# 12mPCIe.net
KiCad netlist of a schematic drawn in Altium Designer
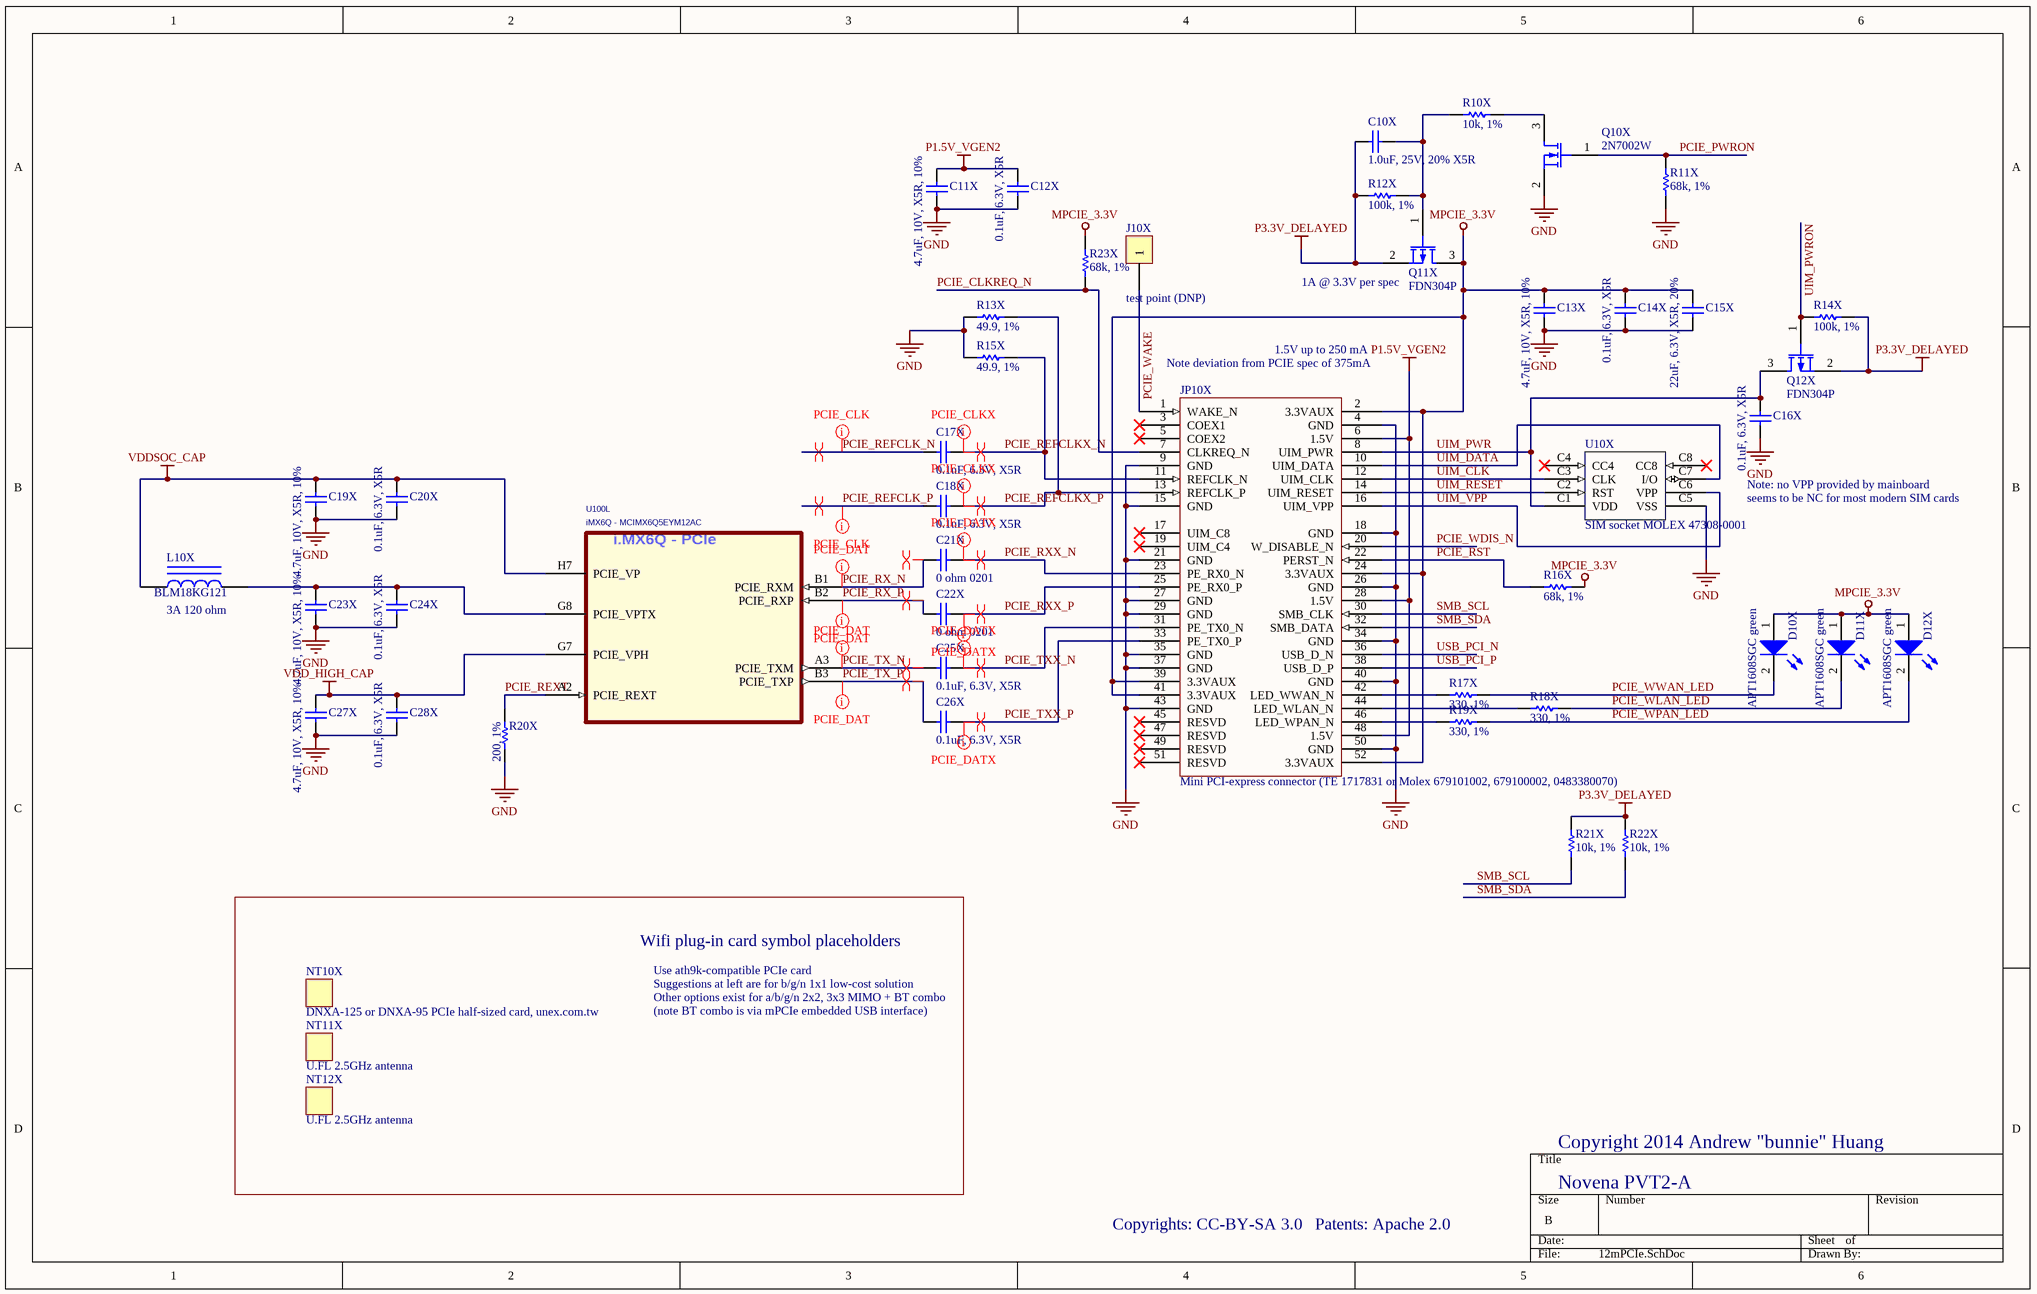
[diagram p0: 12mPCIe.SchDoc]

(export (version "E")
  (design (tool "Eeschema 10.0.6"))
  (components
    (comp (ref "C10X")
      (value "1.0uF, 25V, 20% X5R")
      (footprint "CAPC1608N")
      (description "Capacitor (Semiconductor SIM Model)")
      (fields (field (name "PUBLISHER") "Altium Limited"))
      (libsource (lib "Miscellaneous Devices") (part "Cap Semi"))
    )
    (comp (ref "C11X")
      (value "4.7uF, 10V, X5R, 10%")
      (footprint "CAPC1608N")
      (description "Capacitor (Semiconductor SIM Model)")
      (fields (field (name "PUBLISHER") "Altium Limited"))
      (libsource (lib "Miscellaneous Devices") (part "Cap Semi"))
    )
    (comp (ref "C12X")
      (value "0.1uF, 6.3V, X5R")
      (footprint "CAPC0603N_B")
      (description "Capacitor (Semiconductor SIM Model)")
      (fields (field (name "PUBLISHER") "Altium Limited"))
      (libsource (lib "Miscellaneous Devices") (part "Cap Semi"))
    )
    (comp (ref "C13X")
      (value "4.7uF, 10V, X5R, 10%")
      (footprint "CAPC1608N")
      (description "Capacitor (Semiconductor SIM Model)")
      (fields (field (name "PUBLISHER") "Altium Limited"))
      (libsource (lib "Miscellaneous Devices") (part "Cap Semi"))
    )
    (comp (ref "C14X")
      (value "0.1uF, 6.3V, X5R")
      (footprint "CAPC0603N_B")
      (description "Capacitor (Semiconductor SIM Model)")
      (fields (field (name "PUBLISHER") "Altium Limited"))
      (libsource (lib "Miscellaneous Devices") (part "Cap Semi"))
    )
    (comp (ref "C15X")
      (value "22uF, 6.3V, X5R, 20%")
      (footprint "CAPC1608N_HD")
      (description "Capacitor (Semiconductor SIM Model)")
      (fields (field (name "PUBLISHER") "Altium Limited"))
      (libsource (lib "Miscellaneous Devices") (part "Cap Semi"))
    )
    (comp (ref "C16X")
      (value "0.1uF, 6.3V, X5R")
      (footprint "CAPC0603N_B")
      (description "Capacitor (Semiconductor SIM Model)")
      (fields (field (name "PUBLISHER") "Altium Limited"))
      (libsource (lib "Miscellaneous Devices") (part "Cap Semi"))
    )
    (comp (ref "C17X")
      (value "0.1uF, 6.3V, X5R")
      (footprint "CAPC0603N_B")
      (description "Capacitor (Semiconductor SIM Model)")
      (fields (field (name "PUBLISHER") "Altium Limited"))
      (libsource (lib "Miscellaneous Devices") (part "Cap Semi"))
    )
    (comp (ref "C18X")
      (value "0.1uF, 6.3V, X5R")
      (footprint "CAPC0603N_B")
      (description "Capacitor (Semiconductor SIM Model)")
      (fields (field (name "PUBLISHER") "Altium Limited"))
      (libsource (lib "Miscellaneous Devices") (part "Cap Semi"))
    )
    (comp (ref "C19X")
      (value "4.7uF, 10V, X5R, 10%")
      (footprint "CAPC1608N_HD")
      (description "Capacitor (Semiconductor SIM Model)")
      (fields (field (name "PUBLISHER") "Altium Limited"))
      (libsource (lib "Miscellaneous Devices") (part "Cap Semi"))
    )
    (comp (ref "C20X")
      (value "0.1uF, 6.3V, X5R")
      (footprint "CAPC0603N_B")
      (description "Capacitor (Semiconductor SIM Model)")
      (fields (field (name "PUBLISHER") "Altium Limited"))
      (libsource (lib "Miscellaneous Devices") (part "Cap Semi"))
    )
    (comp (ref "C21X")
      (value "0 ohm 0201")
      (footprint "CAPC0603N_B")
      (description "Capacitor (Semiconductor SIM Model)")
      (fields (field (name "PUBLISHER") "Altium Limited"))
      (libsource (lib "Miscellaneous Devices") (part "Cap Semi"))
    )
    (comp (ref "C22X")
      (value "0 ohm 0201")
      (footprint "CAPC0603N_B")
      (description "Capacitor (Semiconductor SIM Model)")
      (fields (field (name "PUBLISHER") "Altium Limited"))
      (libsource (lib "Miscellaneous Devices") (part "Cap Semi"))
    )
    (comp (ref "C23X")
      (value "4.7uF, 10V, X5R, 10%")
      (footprint "CAPC1608N_HD")
      (description "Capacitor (Semiconductor SIM Model)")
      (fields (field (name "PUBLISHER") "Altium Limited"))
      (libsource (lib "Miscellaneous Devices") (part "Cap Semi"))
    )
    (comp (ref "C24X")
      (value "0.1uF, 6.3V, X5R")
      (footprint "CAPC0603N_B")
      (description "Capacitor (Semiconductor SIM Model)")
      (fields (field (name "PUBLISHER") "Altium Limited"))
      (libsource (lib "Miscellaneous Devices") (part "Cap Semi"))
    )
    (comp (ref "C25X")
      (value "0.1uF, 6.3V, X5R")
      (footprint "CAPC0603N_B")
      (description "Capacitor (Semiconductor SIM Model)")
      (fields (field (name "PUBLISHER") "Altium Limited"))
      (libsource (lib "Miscellaneous Devices") (part "Cap Semi"))
    )
    (comp (ref "C26X")
      (value "0.1uF, 6.3V, X5R")
      (footprint "CAPC0603N_B")
      (description "Capacitor (Semiconductor SIM Model)")
      (fields (field (name "PUBLISHER") "Altium Limited"))
      (libsource (lib "Miscellaneous Devices") (part "Cap Semi"))
    )
    (comp (ref "C27X")
      (value "4.7uF, 10V, X5R, 10%")
      (footprint "CAPC1608N_HD")
      (description "Capacitor (Semiconductor SIM Model)")
      (fields (field (name "PUBLISHER") "Altium Limited"))
      (libsource (lib "Miscellaneous Devices") (part "Cap Semi"))
    )
    (comp (ref "C28X")
      (value "0.1uF, 6.3V, X5R")
      (footprint "CAPC0603N_B")
      (description "Capacitor (Semiconductor SIM Model)")
      (fields (field (name "PUBLISHER") "Altium Limited"))
      (libsource (lib "Miscellaneous Devices") (part "Cap Semi"))
    )
    (comp (ref "D10X")
      (value "APT1608SGC green")
      (footprint "CD1608-0603")
      (description "Typical RED, GREEN, YELLOW, AMBER GaAs LED")
      (fields (field (name "PUBLISHER") "Altium Limited"))
      (libsource (lib "Miscellaneous Devices") (part "LED2"))
    )
    (comp (ref "D11X")
      (value "APT1608SGC green")
      (footprint "CD1608-0603")
      (description "Typical RED, GREEN, YELLOW, AMBER GaAs LED")
      (fields (field (name "PUBLISHER") "Altium Limited"))
      (libsource (lib "Miscellaneous Devices") (part "LED2"))
    )
    (comp (ref "D12X")
      (value "APT1608SGC green")
      (footprint "CD1608-0603")
      (description "Typical RED, GREEN, YELLOW, AMBER GaAs LED")
      (fields (field (name "PUBLISHER") "Altium Limited"))
      (libsource (lib "Miscellaneous Devices") (part "LED2"))
    )
    (comp (ref "J10X")
      (value "test point (DNP)")
      (footprint "TP_SMT_38mil")
      (description "Connector")
      (libsource (lib "*") (part "CON1"))
    )
    (comp (ref "JP10X")
      (value "Mini PCI-express connector (TE 1717831 or Molex 679101002, 679100002, 0483380070)")
      (footprint "MPCI_FULL_TE_1717831")
      (description "Mini PCI-express, e.g. TE 1717831")
      (libsource (lib "commonsch") (part "MINI_PCIE"))
    )
    (comp (ref "L10X")
      (value "BLM18KG121")
      (footprint "INDC1608AN")
      (description "Magnetic-Core Inductor")
      (fields (field (name "ALTIUM_VALUE") "3A 120 ohm") (field (name "PUBLISHER") "Altium Limited"))
      (libsource (lib "Miscellaneous Devices") (part "Inductor Iron"))
    )
    (comp (ref "NT10X")
      (value "DNXA-125 or DNXA-95 PCIe half-sized card, unex.com.tw")
      (description "Placeholder for non-electrical BOM items")
      (libsource (lib "commonsch") (part "NOTE"))
    )
    (comp (ref "NT11X")
      (value "U.FL 2.5GHz antenna")
      (description "Placeholder for non-electrical BOM items")
      (libsource (lib "commonsch") (part "NOTE"))
    )
    (comp (ref "NT12X")
      (value "U.FL 2.5GHz antenna")
      (description "Placeholder for non-electrical BOM items")
      (libsource (lib "commonsch") (part "NOTE"))
    )
    (comp (ref "Q10X")
      (value "2N7002W")
      (footprint "SOT323-3AN")
      (description "N-Channel MOSFET")
      (fields (field (name "PUBLISHER") "Altium Limited"))
      (libsource (lib "Miscellaneous Devices") (part "MOSFET-N"))
    )
    (comp (ref "Q11X")
      (value "FDN304P")
      (footprint "SOT23-3N")
      (description "P-Channel MOSFET")
      (fields (field (name "PUBLISHER") "Altium Limited"))
      (libsource (lib "Miscellaneous Devices") (part "MOSFET-P"))
    )
    (comp (ref "Q12X")
      (value "FDN304P")
      (footprint "SOT23-3N")
      (description "P-Channel MOSFET")
      (fields (field (name "PUBLISHER") "Altium Limited"))
      (libsource (lib "Miscellaneous Devices") (part "MOSFET-P"))
    )
    (comp (ref "R10X")
      (value "10k, 1%")
      (footprint "RESC1005N")
      (description "Resistor")
      (fields (field (name "PUBLISHER") "Altium Limited"))
      (libsource (lib "Miscellaneous Devices") (part "Res1"))
    )
    (comp (ref "R11X")
      (value "68k, 1%")
      (footprint "RESC1005N")
      (description "Resistor")
      (fields (field (name "PUBLISHER") "Altium Limited"))
      (libsource (lib "Miscellaneous Devices") (part "Res1"))
    )
    (comp (ref "R12X")
      (value "100k, 1%")
      (footprint "RESC1005N")
      (description "Resistor")
      (fields (field (name "PUBLISHER") "Altium Limited"))
      (libsource (lib "Miscellaneous Devices") (part "Res1"))
    )
    (comp (ref "R13X")
      (value "49.9, 1%")
      (footprint "RESC1005N")
      (description "Resistor")
      (fields (field (name "PUBLISHER") "Altium Limited"))
      (libsource (lib "Miscellaneous Devices") (part "Res1"))
    )
    (comp (ref "R14X")
      (value "100k, 1%")
      (footprint "RESC1005N")
      (description "Resistor")
      (fields (field (name "PUBLISHER") "Altium Limited"))
      (libsource (lib "Miscellaneous Devices") (part "Res1"))
    )
    (comp (ref "R15X")
      (value "49.9, 1%")
      (footprint "RESC1005N")
      (description "Resistor")
      (fields (field (name "PUBLISHER") "Altium Limited"))
      (libsource (lib "Miscellaneous Devices") (part "Res1"))
    )
    (comp (ref "R16X")
      (value "68k, 1%")
      (footprint "RESC1005N")
      (description "Resistor")
      (fields (field (name "PUBLISHER") "Altium Limited"))
      (libsource (lib "Miscellaneous Devices") (part "Res1"))
    )
    (comp (ref "R17X")
      (value "330, 1%")
      (footprint "RESC1005N")
      (description "Resistor")
      (fields (field (name "PUBLISHER") "Altium Limited"))
      (libsource (lib "Miscellaneous Devices") (part "Res1"))
    )
    (comp (ref "R18X")
      (value "330, 1%")
      (footprint "RESC1005N")
      (description "Resistor")
      (fields (field (name "PUBLISHER") "Altium Limited"))
      (libsource (lib "Miscellaneous Devices") (part "Res1"))
    )
    (comp (ref "R19X")
      (value "330, 1%")
      (footprint "RESC1005N")
      (description "Resistor")
      (fields (field (name "PUBLISHER") "Altium Limited"))
      (libsource (lib "Miscellaneous Devices") (part "Res1"))
    )
    (comp (ref "R20X")
      (value "200, 1%")
      (footprint "RESC1005N")
      (description "Resistor")
      (fields (field (name "PUBLISHER") "Altium Limited"))
      (libsource (lib "Miscellaneous Devices") (part "Res1"))
    )
    (comp (ref "R21X")
      (value "10k, 1%")
      (footprint "RESC1005N")
      (description "Resistor")
      (fields (field (name "PUBLISHER") "Altium Limited"))
      (libsource (lib "Miscellaneous Devices") (part "Res1"))
    )
    (comp (ref "R22X")
      (value "10k, 1%")
      (footprint "RESC1005N")
      (description "Resistor")
      (fields (field (name "PUBLISHER") "Altium Limited"))
      (libsource (lib "Miscellaneous Devices") (part "Res1"))
    )
    (comp (ref "R23X")
      (value "68k, 1%")
      (footprint "RESC1005N")
      (description "Resistor")
      (fields (field (name "PUBLISHER") "Altium Limited"))
      (libsource (lib "Miscellaneous Devices") (part "Res1"))
    )
    (comp (ref "U10X")
      (value "SIM socket MOLEX 47308-0001")
      (footprint "MOLEX_SIM_47308-001")
      (description "ISO 7816 SIM card socket")
      (libsource (lib "commonsch") (part "ISO7816 (SIM card)"))
    )
    (comp (ref "U100")
      (value "iMX6Q - MCIMX6Q5EYM12AC")
      (description "PCIMX6Q5EVT10AC")
      (libsource (lib "*") (part "PCIMX6Q6VV1A"))
    )
  )
  (nets
    (net (code "1") (name "/PCIE_CLKREQ_N") (class "Default")
      (node (ref "JP10X") (pin "7") (pinfunction "CLKREQ_N_7") (pintype "passive"))
      (node (ref "R23X") (pin "1") (pinfunction "1_1") (pintype "passive"))
    )
    (net (code "2") (name "/PCIE_PWRON") (class "Default")
      (node (ref "Q10X") (pin "1") (pinfunction "G_1") (pintype "passive"))
      (node (ref "R11X") (pin "1") (pinfunction "1_1") (pintype "passive"))
    )
    (net (code "3") (name "/PCIE_REFCLKX_N") (class "Default")
      (node (ref "C17X") (pin "1") (pinfunction "1_1") (pintype "passive"))
      (node (ref "JP10X") (pin "11") (pinfunction "REFCLK_N_11") (pintype "input"))
      (node (ref "R15X") (pin "1") (pinfunction "1_1") (pintype "passive"))
    )
    (net (code "4") (name "/PCIE_REFCLKX_P") (class "Default")
      (node (ref "C18X") (pin "1") (pinfunction "1_1") (pintype "passive"))
      (node (ref "JP10X") (pin "13") (pinfunction "REFCLK_P_13") (pintype "input"))
      (node (ref "R13X") (pin "1") (pinfunction "1_1") (pintype "passive"))
    )
    (net (code "5") (name "/PCIE_REFCLK_N") (class "Default")
      (node (ref "C17X") (pin "2") (pinfunction "2_2") (pintype "passive"))
    )
    (net (code "6") (name "/PCIE_REFCLK_P") (class "Default")
      (node (ref "C18X") (pin "2") (pinfunction "2_2") (pintype "passive"))
    )
    (net (code "7") (name "/PCIE_REXT") (class "Default")
      (node (ref "R20X") (pin "2") (pinfunction "2_2") (pintype "passive"))
      (node (ref "U100") (pin "A2") (pinfunction "PCIE_REXT_A2") (pintype "input"))
    )
    (net (code "8") (name "/PCIE_RST") (class "Default")
      (node (ref "JP10X") (pin "22") (pinfunction "PERST_N_22") (pintype "input"))
      (node (ref "R16X") (pin "2") (pinfunction "2_2") (pintype "passive"))
    )
    (net (code "9") (name "/PCIE_RXX_N") (class "Default")
      (node (ref "C21X") (pin "1") (pinfunction "1_1") (pintype "passive"))
      (node (ref "JP10X") (pin "23") (pinfunction "PE_RX0_N_23") (pintype "passive"))
    )
    (net (code "10") (name "/PCIE_RXX_P") (class "Default")
      (node (ref "C22X") (pin "1") (pinfunction "1_1") (pintype "passive"))
      (node (ref "JP10X") (pin "25") (pinfunction "PE_RX0_P_25") (pintype "passive"))
    )
    (net (code "11") (name "/PCIE_RX_N") (class "Default")
      (node (ref "C21X") (pin "2") (pinfunction "2_2") (pintype "passive"))
      (node (ref "U100") (pin "B1") (pinfunction "PCIE_RXM_B1") (pintype "input"))
    )
    (net (code "12") (name "/PCIE_RX_P") (class "Default")
      (node (ref "C22X") (pin "2") (pinfunction "2_2") (pintype "passive"))
      (node (ref "U100") (pin "B2") (pinfunction "PCIE_RXP_B2") (pintype "input"))
    )
    (net (code "13") (name "/PCIE_TXX_N") (class "Default")
      (node (ref "C25X") (pin "1") (pinfunction "1_1") (pintype "passive"))
      (node (ref "JP10X") (pin "31") (pinfunction "PE_TX0_N_31") (pintype "passive"))
    )
    (net (code "14") (name "/PCIE_TXX_P") (class "Default")
      (node (ref "C26X") (pin "1") (pinfunction "1_1") (pintype "passive"))
      (node (ref "JP10X") (pin "33") (pinfunction "PE_TX0_P_33") (pintype "passive"))
    )
    (net (code "15") (name "/PCIE_TX_N") (class "Default")
      (node (ref "C25X") (pin "2") (pinfunction "2_2") (pintype "passive"))
      (node (ref "U100") (pin "A3") (pinfunction "PCIE_TXM_A3") (pintype "output"))
    )
    (net (code "16") (name "/PCIE_TX_P") (class "Default")
      (node (ref "C26X") (pin "2") (pinfunction "2_2") (pintype "passive"))
      (node (ref "U100") (pin "B3") (pinfunction "PCIE_TXP_B3") (pintype "output"))
    )
    (net (code "17") (name "/PCIE_WAKE") (class "Default")
      (node (ref "J10X") (pin "1") (pinfunction "1_1") (pintype "passive"))
      (node (ref "JP10X") (pin "1") (pinfunction "WAKE_N_1") (pintype "input"))
    )
    (net (code "18") (name "/PCIE_WDIS_N") (class "Default")
      (node (ref "JP10X") (pin "20") (pinfunction "W_DISABLE_N_20") (pintype "input"))
    )
    (net (code "19") (name "/PCIE_WLAN_LED") (class "Default")
      (node (ref "D11X") (pin "2") (pinfunction "K_2") (pintype "passive"))
      (node (ref "R18X") (pin "2") (pinfunction "2_2") (pintype "passive"))
    )
    (net (code "20") (name "/PCIE_WPAN_LED") (class "Default")
      (node (ref "D12X") (pin "2") (pinfunction "K_2") (pintype "passive"))
      (node (ref "R19X") (pin "2") (pinfunction "2_2") (pintype "passive"))
    )
    (net (code "21") (name "/PCIE_WWAN_LED") (class "Default")
      (node (ref "D10X") (pin "2") (pinfunction "K_2") (pintype "passive"))
      (node (ref "R17X") (pin "2") (pinfunction "2_2") (pintype "passive"))
    )
    (net (code "22") (name "/SMB_SCL") (class "Default")
      (node (ref "JP10X") (pin "30") (pinfunction "SMB_CLK_30") (pintype "input"))
      (node (ref "R21X") (pin "1") (pinfunction "1_1") (pintype "passive"))
    )
    (net (code "23") (name "/SMB_SDA") (class "Default")
      (node (ref "JP10X") (pin "32") (pinfunction "SMB_DATA_32") (pintype "input"))
      (node (ref "R22X") (pin "1") (pinfunction "1_1") (pintype "passive"))
    )
    (net (code "24") (name "/UIM_CLK") (class "Default")
      (node (ref "JP10X") (pin "12") (pinfunction "UIM_CLK_12") (pintype "passive"))
      (node (ref "U10X") (pin "C3") (pinfunction "CLK_C3") (pintype "input"))
    )
    (net (code "25") (name "/UIM_DATA") (class "Default")
      (node (ref "JP10X") (pin "10") (pinfunction "UIM_DATA_10") (pintype "passive"))
      (node (ref "U10X") (pin "C7") (pinfunction "I/O_C7") (pintype "bidirectional"))
    )
    (net (code "26") (name "/UIM_PWR") (class "Default")
      (node (ref "C16X") (pin "1") (pinfunction "1_1") (pintype "passive"))
      (node (ref "JP10X") (pin "8") (pinfunction "UIM_PWR_8") (pintype "passive"))
      (node (ref "Q12X") (pin "3") (pinfunction "D_3") (pintype "passive"))
      (node (ref "U10X") (pin "C1") (pinfunction "VDD_C1") (pintype "power_in"))
    )
    (net (code "27") (name "/UIM_PWRON") (class "Default")
      (node (ref "Q12X") (pin "1") (pinfunction "G_1") (pintype "passive"))
      (node (ref "R14X") (pin "2") (pinfunction "2_2") (pintype "passive"))
    )
    (net (code "28") (name "/UIM_RESET") (class "Default")
      (node (ref "JP10X") (pin "14") (pinfunction "UIM_RESET_14") (pintype "passive"))
      (node (ref "U10X") (pin "C2") (pinfunction "RST_C2") (pintype "input"))
    )
    (net (code "29") (name "/UIM_VPP") (class "Default")
      (node (ref "JP10X") (pin "16") (pinfunction "UIM_VPP_16") (pintype "passive"))
      (node (ref "U10X") (pin "C6") (pinfunction "VPP_C6") (pintype "power_in"))
    )
    (net (code "30") (name "/USB_PCI_N") (class "Default")
      (node (ref "JP10X") (pin "36") (pinfunction "USB_D_N_36") (pintype "passive"))
    )
    (net (code "31") (name "/USB_PCI_P") (class "Default")
      (node (ref "JP10X") (pin "38") (pinfunction "USB_D_P_38") (pintype "passive"))
    )
    (net (code "32") (name "GND") (class "Default")
      (node (ref "C11X") (pin "2") (pinfunction "2_2") (pintype "passive"))
      (node (ref "C12X") (pin "2") (pinfunction "2_2") (pintype "passive"))
      (node (ref "C13X") (pin "2") (pinfunction "2_2") (pintype "passive"))
      (node (ref "C14X") (pin "2") (pinfunction "2_2") (pintype "passive"))
      (node (ref "C15X") (pin "2") (pinfunction "2_2") (pintype "passive"))
      (node (ref "C16X") (pin "2") (pinfunction "2_2") (pintype "passive"))
      (node (ref "C19X") (pin "2") (pinfunction "2_2") (pintype "passive"))
      (node (ref "C20X") (pin "2") (pinfunction "2_2") (pintype "passive"))
      (node (ref "C23X") (pin "2") (pinfunction "2_2") (pintype "passive"))
      (node (ref "C24X") (pin "2") (pinfunction "2_2") (pintype "passive"))
      (node (ref "C27X") (pin "2") (pinfunction "2_2") (pintype "passive"))
      (node (ref "C28X") (pin "2") (pinfunction "2_2") (pintype "passive"))
      (node (ref "JP10X") (pin "15") (pinfunction "GND_15") (pintype "power_in"))
      (node (ref "JP10X") (pin "18") (pinfunction "GND_18") (pintype "power_in"))
      (node (ref "JP10X") (pin "21") (pinfunction "GND_21") (pintype "power_in"))
      (node (ref "JP10X") (pin "26") (pinfunction "GND_26") (pintype "power_in"))
      (node (ref "JP10X") (pin "27") (pinfunction "GND_27") (pintype "power_in"))
      (node (ref "JP10X") (pin "29") (pinfunction "GND_29") (pintype "power_in"))
      (node (ref "JP10X") (pin "34") (pinfunction "GND_34") (pintype "power_in"))
      (node (ref "JP10X") (pin "35") (pinfunction "GND_35") (pintype "power_in"))
      (node (ref "JP10X") (pin "37") (pinfunction "GND_37") (pintype "power_in"))
      (node (ref "JP10X") (pin "4") (pinfunction "GND_4") (pintype "power_in"))
      (node (ref "JP10X") (pin "40") (pinfunction "GND_40") (pintype "power_in"))
      (node (ref "JP10X") (pin "43") (pinfunction "GND_43") (pintype "power_in"))
      (node (ref "JP10X") (pin "50") (pinfunction "GND_50") (pintype "power_in"))
      (node (ref "JP10X") (pin "9") (pinfunction "GND_9") (pintype "power_in"))
      (node (ref "Q10X") (pin "2") (pinfunction "S_2") (pintype "passive"))
      (node (ref "R11X") (pin "2") (pinfunction "2_2") (pintype "passive"))
      (node (ref "R13X") (pin "2") (pinfunction "2_2") (pintype "passive"))
      (node (ref "R15X") (pin "2") (pinfunction "2_2") (pintype "passive"))
      (node (ref "R20X") (pin "1") (pinfunction "1_1") (pintype "passive"))
      (node (ref "U10X") (pin "C5") (pinfunction "VSS_C5") (pintype "power_in"))
    )
    (net (code "33") (name "MPCIE_3.3V") (class "Default")
      (node (ref "C13X") (pin "1") (pinfunction "1_1") (pintype "passive"))
      (node (ref "C14X") (pin "1") (pinfunction "1_1") (pintype "passive"))
      (node (ref "C15X") (pin "1") (pinfunction "1_1") (pintype "passive"))
      (node (ref "D10X") (pin "1") (pinfunction "A_1") (pintype "passive"))
      (node (ref "D11X") (pin "1") (pinfunction "A_1") (pintype "passive"))
      (node (ref "D12X") (pin "1") (pinfunction "A_1") (pintype "passive"))
      (node (ref "JP10X") (pin "2") (pinfunction "3.3VAUX_2") (pintype "power_in"))
      (node (ref "JP10X") (pin "24") (pinfunction "3.3VAUX_24") (pintype "power_in"))
      (node (ref "JP10X") (pin "39") (pinfunction "3.3VAUX_39") (pintype "power_in"))
      (node (ref "JP10X") (pin "41") (pinfunction "3.3VAUX_41") (pintype "power_in"))
      (node (ref "JP10X") (pin "52") (pinfunction "3.3VAUX_52") (pintype "power_in"))
      (node (ref "Q11X") (pin "3") (pinfunction "D_3") (pintype "passive"))
      (node (ref "R16X") (pin "1") (pinfunction "1_1") (pintype "passive"))
      (node (ref "R23X") (pin "2") (pinfunction "2_2") (pintype "passive"))
    )
    (net (code "34") (name "Net-(JP10X-LED_WLAN_N)") (class "Default")
      (node (ref "JP10X") (pin "44") (pinfunction "LED_WLAN_N_44") (pintype "passive"))
      (node (ref "R18X") (pin "1") (pinfunction "1_1") (pintype "passive"))
    )
    (net (code "35") (name "Net-(JP10X-LED_WPAN_N)") (class "Default")
      (node (ref "JP10X") (pin "46") (pinfunction "LED_WPAN_N_46") (pintype "passive"))
      (node (ref "R19X") (pin "1") (pinfunction "1_1") (pintype "passive"))
    )
    (net (code "36") (name "Net-(JP10X-LED_WWAN_N)") (class "Default")
      (node (ref "JP10X") (pin "42") (pinfunction "LED_WWAN_N_42") (pintype "passive"))
      (node (ref "R17X") (pin "1") (pinfunction "1_1") (pintype "passive"))
    )
    (net (code "37") (name "Net-(Q10X-D)") (class "Default")
      (node (ref "Q10X") (pin "3") (pinfunction "D_3") (pintype "passive"))
      (node (ref "R10X") (pin "2") (pinfunction "2_2") (pintype "passive"))
    )
    (net (code "38") (name "Net-(Q11X-G)") (class "Default")
      (node (ref "C10X") (pin "1") (pinfunction "1_1") (pintype "passive"))
      (node (ref "Q11X") (pin "1") (pinfunction "G_1") (pintype "passive"))
      (node (ref "R10X") (pin "1") (pinfunction "1_1") (pintype "passive"))
      (node (ref "R12X") (pin "1") (pinfunction "1_1") (pintype "passive"))
    )
    (net (code "39") (name "Net-(U100L-PCIE_VPTX)") (class "Default")
      (node (ref "C23X") (pin "1") (pinfunction "1_1") (pintype "passive"))
      (node (ref "C24X") (pin "1") (pinfunction "1_1") (pintype "passive"))
      (node (ref "L10X") (pin "2") (pinfunction "2_2") (pintype "passive"))
      (node (ref "U100") (pin "G8") (pinfunction "PCIE_VPTX_G8") (pintype "power_in"))
    )
    (net (code "40") (name "P1.5V_VGEN2") (class "Default")
      (node (ref "C11X") (pin "1") (pinfunction "1_1") (pintype "passive"))
      (node (ref "C12X") (pin "1") (pinfunction "1_1") (pintype "passive"))
      (node (ref "JP10X") (pin "28") (pinfunction "1.5V_28") (pintype "power_in"))
      (node (ref "JP10X") (pin "48") (pinfunction "1.5V_48") (pintype "power_in"))
      (node (ref "JP10X") (pin "6") (pinfunction "1.5V_6") (pintype "power_in"))
    )
    (net (code "41") (name "P3.3V_DELAYED") (class "Default")
      (node (ref "C10X") (pin "2") (pinfunction "2_2") (pintype "passive"))
      (node (ref "Q11X") (pin "2") (pinfunction "S_2") (pintype "passive"))
      (node (ref "Q12X") (pin "2") (pinfunction "S_2") (pintype "passive"))
      (node (ref "R12X") (pin "2") (pinfunction "2_2") (pintype "passive"))
      (node (ref "R14X") (pin "1") (pinfunction "1_1") (pintype "passive"))
      (node (ref "R21X") (pin "2") (pinfunction "2_2") (pintype "passive"))
      (node (ref "R22X") (pin "2") (pinfunction "2_2") (pintype "passive"))
    )
    (net (code "42") (name "VDDSOC_CAP") (class "Default")
      (node (ref "C19X") (pin "1") (pinfunction "1_1") (pintype "passive"))
      (node (ref "C20X") (pin "1") (pinfunction "1_1") (pintype "passive"))
      (node (ref "L10X") (pin "1") (pinfunction "1_1") (pintype "passive"))
      (node (ref "U100") (pin "H7") (pinfunction "PCIE_VP_H7") (pintype "power_in"))
    )
    (net (code "43") (name "VDD_HIGH_CAP") (class "Default")
      (node (ref "C27X") (pin "1") (pinfunction "1_1") (pintype "passive"))
      (node (ref "C28X") (pin "1") (pinfunction "1_1") (pintype "passive"))
      (node (ref "U100") (pin "G7") (pinfunction "PCIE_VPH_G7") (pintype "power_in"))
    )
    (net (code "44") (name "unconnected-(JP10X-COEX1-Pad3)") (class "Default")
      (node (ref "JP10X") (pin "3") (pinfunction "COEX1_3") (pintype "passive+no_connect"))
    )
    (net (code "45") (name "unconnected-(JP10X-COEX2-Pad5)") (class "Default")
      (node (ref "JP10X") (pin "5") (pinfunction "COEX2_5") (pintype "passive+no_connect"))
    )
    (net (code "46") (name "unconnected-(JP10X-RESVD-Pad45)") (class "Default")
      (node (ref "JP10X") (pin "45") (pinfunction "RESVD_45") (pintype "passive+no_connect"))
    )
    (net (code "47") (name "unconnected-(JP10X-RESVD-Pad47)") (class "Default")
      (node (ref "JP10X") (pin "47") (pinfunction "RESVD_47") (pintype "passive+no_connect"))
    )
    (net (code "48") (name "unconnected-(JP10X-RESVD-Pad49)") (class "Default")
      (node (ref "JP10X") (pin "49") (pinfunction "RESVD_49") (pintype "passive+no_connect"))
    )
    (net (code "49") (name "unconnected-(JP10X-RESVD-Pad51)") (class "Default")
      (node (ref "JP10X") (pin "51") (pinfunction "RESVD_51") (pintype "passive+no_connect"))
    )
    (net (code "50") (name "unconnected-(JP10X-UIM_C4-Pad19)") (class "Default")
      (node (ref "JP10X") (pin "19") (pinfunction "UIM_C4_19") (pintype "passive+no_connect"))
    )
    (net (code "51") (name "unconnected-(JP10X-UIM_C8-Pad17)") (class "Default")
      (node (ref "JP10X") (pin "17") (pinfunction "UIM_C8_17") (pintype "passive+no_connect"))
    )
    (net (code "52") (name "unconnected-(U10X-CC4-PadC4)") (class "Default")
      (node (ref "U10X") (pin "C4") (pinfunction "CC4_C4") (pintype "input+no_connect"))
    )
    (net (code "53") (name "unconnected-(U10X-CC8-PadC8)") (class "Default")
      (node (ref "U10X") (pin "C8") (pinfunction "CC8_C8") (pintype "input+no_connect"))
    )
  )
)
